# batteryboard-v2_2.net
KiCad netlist of a schematic drawn in EAGLE
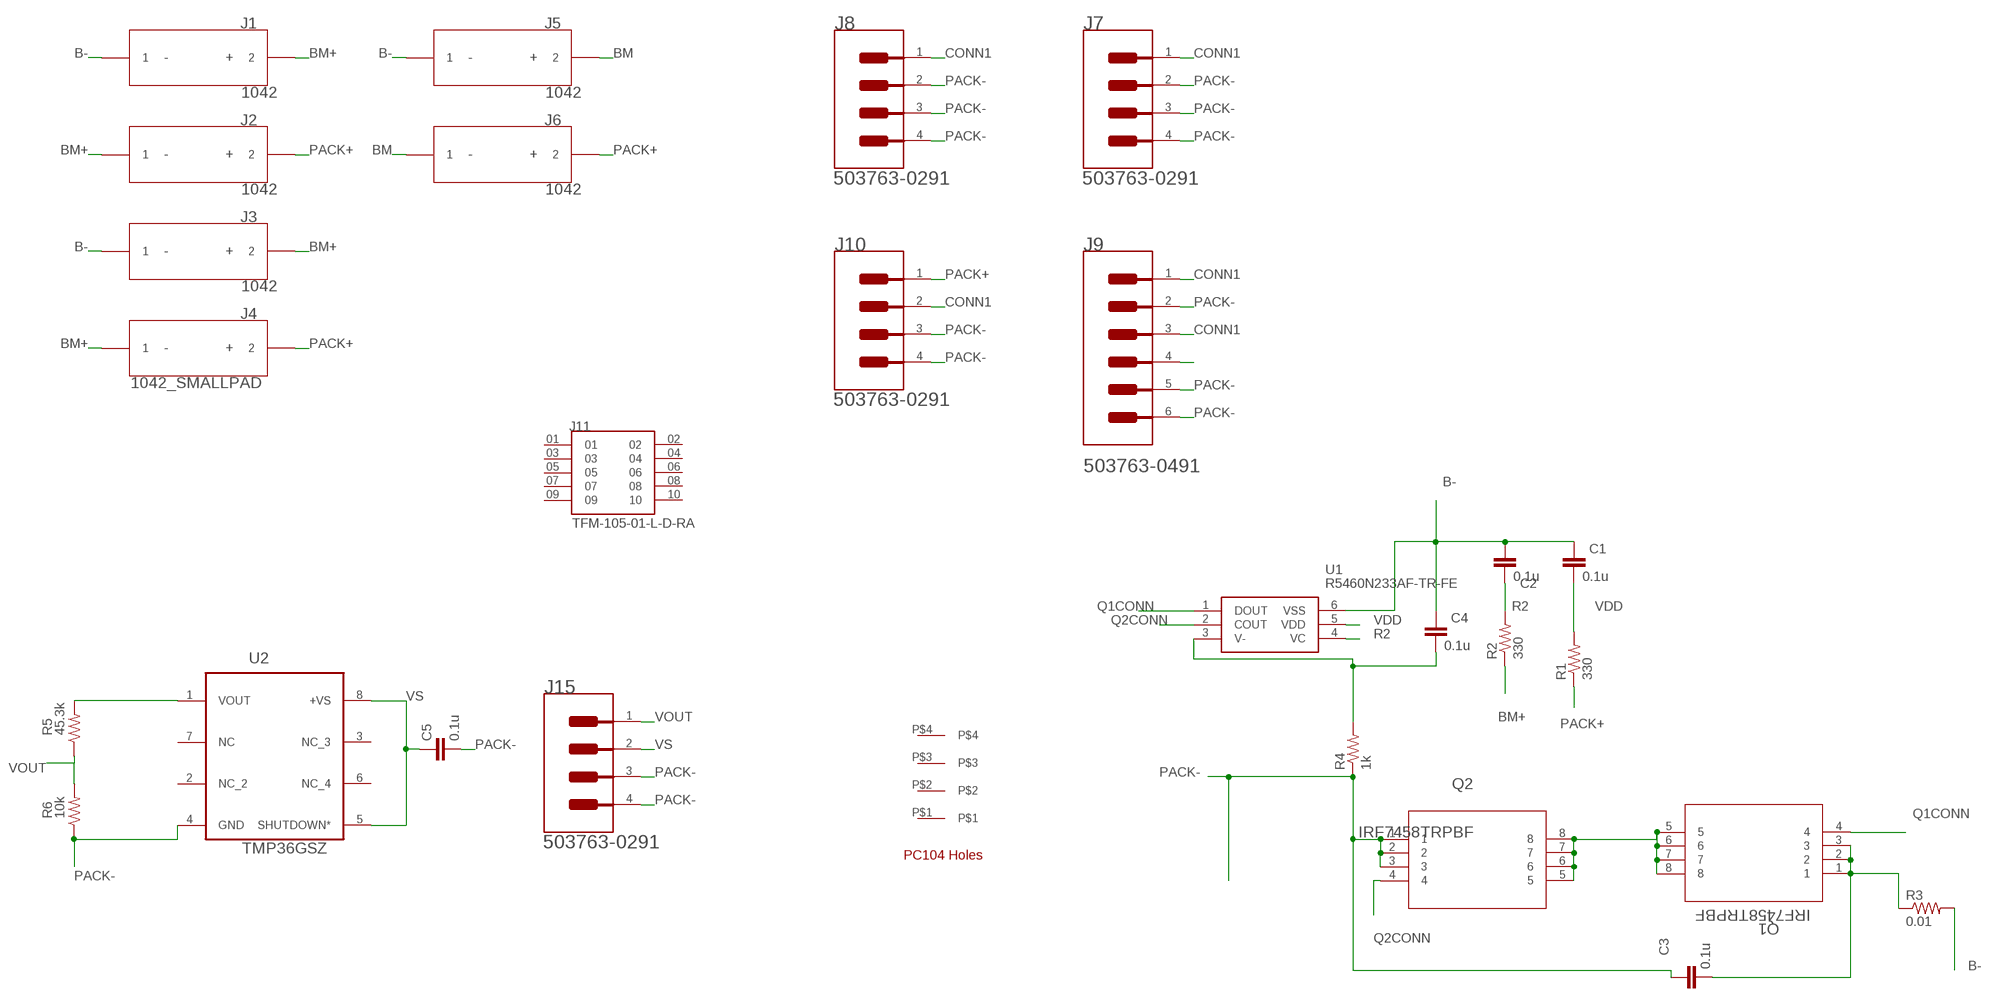
[diagram p0: schematic, sheet 1]

(export (version "E")
  (design (tool "Eeschema 10.0.6"))
  (components
    (comp (ref "C1")
      (value "0.1u")
      (footprint "eagle-import:0603-CAP")
      (libsource (lib "eagle-import") (part "CAP0603-CAP"))
    )
    (comp (ref "C2")
      (value "0.1u")
      (footprint "eagle-import:0603-CAP")
      (libsource (lib "eagle-import") (part "CAP0603-CAP"))
    )
    (comp (ref "C3")
      (value "0.1u")
      (footprint "eagle-import:0603-CAP")
      (libsource (lib "eagle-import") (part "CAP0603-CAP"))
    )
    (comp (ref "C4")
      (value "0.1u")
      (footprint "eagle-import:0603-CAP")
      (libsource (lib "eagle-import") (part "CAP0603-CAP"))
    )
    (comp (ref "C5")
      (value "0.1u")
      (footprint "eagle-import:0805")
      (libsource (lib "eagle-import") (part "CAP0805"))
    )
    (comp (ref "J1")
      (value "1042")
      (footprint "eagle-import:1042_KEY")
      (fields (field (name "COPYRIGHT") "Copyright (C) 2021 Ultra Librarian. All rights reserved."))
      (libsource (lib "eagle-import") (part "1042"))
    )
    (comp (ref "J2")
      (value "1042")
      (footprint "eagle-import:1042_KEY")
      (fields (field (name "COPYRIGHT") "Copyright (C) 2021 Ultra Librarian. All rights reserved."))
      (libsource (lib "eagle-import") (part "1042"))
    )
    (comp (ref "J3")
      (value "1042")
      (footprint "eagle-import:1042_KEY")
      (fields (field (name "COPYRIGHT") "Copyright (C) 2021 Ultra Librarian. All rights reserved."))
      (libsource (lib "eagle-import") (part "1042"))
    )
    (comp (ref "J4")
      (value "1042_SMALLPAD")
      (footprint "eagle-import:1042_KEY_SMALLPAD")
      (libsource (lib "eagle-import") (part "1042_SMALLPAD"))
    )
    (comp (ref "J5")
      (value "1042")
      (footprint "eagle-import:1042_KEY")
      (fields (field (name "COPYRIGHT") "Copyright (C) 2021 Ultra Librarian. All rights reserved."))
      (libsource (lib "eagle-import") (part "1042"))
    )
    (comp (ref "J6")
      (value "1042")
      (footprint "eagle-import:1042_KEY")
      (fields (field (name "COPYRIGHT") "Copyright (C) 2021 Ultra Librarian. All rights reserved."))
      (libsource (lib "eagle-import") (part "1042"))
    )
    (comp (ref "J7")
      (value "MOLEX_503763-0291MOLEX_503763-0291_0_0")
      (footprint "eagle-import:MOLEX_503763-0291_0")
      (fields
        (field (name "DIGIKEY_PART_NUMBER") "WM10654CT-ND")
        (field (name "MF") "Molex")
        (field (name "MOUSER_PART_NUMBER") "538-503763-0291")
      )
      (libsource (lib "eagle-import") (part "MOLEX_503763-0291MOLEX_503763-0291_0_0"))
    )
    (comp (ref "J8")
      (value "MOLEX_503763-0291MOLEX_503763-0291_0_0")
      (footprint "eagle-import:MOLEX_503763-0291_0")
      (fields
        (field (name "DIGIKEY_PART_NUMBER") "WM10654CT-ND")
        (field (name "MF") "Molex")
        (field (name "MOUSER_PART_NUMBER") "538-503763-0291")
      )
      (libsource (lib "eagle-import") (part "MOLEX_503763-0291MOLEX_503763-0291_0_0"))
    )
    (comp (ref "J9")
      (value "MOLEX_503763-0491MOLEX_503763-0491_0_0")
      (footprint "eagle-import:MOLEX_503763-0491_0")
      (fields
        (field (name "DIGIKEY_PART_NUMBER") "WM10655CT-ND")
        (field (name "MF") "Molex")
        (field (name "MOUSER_PART_NUMBER") "538-503763-0491")
      )
      (libsource (lib "eagle-import") (part "MOLEX_503763-0491MOLEX_503763-0491_0_0"))
    )
    (comp (ref "J10")
      (value "MOLEX_503763-0291MOLEX_503763-0291_0_0")
      (footprint "eagle-import:MOLEX_503763-0291_0")
      (fields
        (field (name "DIGIKEY_PART_NUMBER") "WM10654CT-ND")
        (field (name "MF") "Molex")
        (field (name "MOUSER_PART_NUMBER") "538-503763-0291")
      )
      (libsource (lib "eagle-import") (part "MOLEX_503763-0291MOLEX_503763-0291_0_0"))
    )
    (comp (ref "J11")
      (value "TFM-105-01-L-D-RA")
      (footprint "eagle-import:SAMTEC_TFM-105-01-L-D-RA")
      (fields (field (name "MANUFACTURER") "Samtec"))
      (libsource (lib "eagle-import") (part "TFM-105-01-L-D-RA"))
    )
    (comp (ref "J15")
      (value "MOLEX_503763-0291MOLEX_503763-0291_0_0")
      (footprint "eagle-import:MOLEX_503763-0291_0")
      (fields
        (field (name "DIGIKEY_PART_NUMBER") "WM10654CT-ND")
        (field (name "MF") "Molex")
        (field (name "MOUSER_PART_NUMBER") "538-503763-0291")
      )
      (libsource (lib "eagle-import") (part "MOLEX_503763-0291MOLEX_503763-0291_0_0"))
    )
    (comp (ref "Q1")
      (value "IRF7458TRPBF")
      (footprint "eagle-import:SO-8_IRF7458_3P9X4P9_INF")
      (fields (field (name "COPYRIGHT") "Copyright (C) 2021 Ultra Librarian. All rights reserved."))
      (libsource (lib "eagle-import") (part "IRF7458TRPBF"))
    )
    (comp (ref "Q2")
      (value "IRF7458TRPBF")
      (footprint "eagle-import:SO-8_IRF7458_3P9X4P9_INF")
      (fields (field (name "COPYRIGHT") "Copyright (C) 2021 Ultra Librarian. All rights reserved."))
      (libsource (lib "eagle-import") (part "IRF7458TRPBF"))
    )
    (comp (ref "R1")
      (value "330")
      (footprint "eagle-import:0603-RES")
      (libsource (lib "eagle-import") (part "RESISTOR0603-RES"))
    )
    (comp (ref "R2")
      (value "330")
      (footprint "eagle-import:0603-RES")
      (libsource (lib "eagle-import") (part "RESISTOR0603-RES"))
    )
    (comp (ref "R3")
      (value "0.01")
      (footprint "eagle-import:R2512")
      (libsource (lib "eagle-import") (part "RESISTOR2512"))
    )
    (comp (ref "R4")
      (value "1k")
      (footprint "eagle-import:0603-RES")
      (libsource (lib "eagle-import") (part "RESISTOR0603-RES"))
    )
    (comp (ref "R5")
      (value "45.3k")
      (footprint "eagle-import:0805")
      (libsource (lib "eagle-import") (part "RESISTOR0805-RES"))
    )
    (comp (ref "R6")
      (value "10k")
      (footprint "eagle-import:0805")
      (libsource (lib "eagle-import") (part "RESISTOR0805-RES"))
    )
    (comp (ref "U$1")
      (value "PC104_HOLES")
      (footprint "eagle-import:PC104_HOLES")
      (libsource (lib "eagle-import") (part "PC104_HOLES"))
    )
    (comp (ref "U1")
      (value "R5460N233AF-TR-FE")
      (footprint "eagle-import:SOT95P280X140-6N")
      (fields (field (name "MOUSER_PART_NUMBER") "848-R5460N233AFTRFE"))
      (libsource (lib "eagle-import") (part "R5460N233AF-TR-FE"))
    )
    (comp (ref "U2")
      (value "TMP36GSZ")
      (footprint "eagle-import:SOIC127P600X175-8N")
      (fields (field (name "MF") "Analog Devices"))
      (libsource (lib "eagle-import") (part "TMP36GSZ"))
    )
  )
  (nets
    (net (code "1") (name "/B-") (class "Default")
      (node (ref "C1") (pin "1") (pinfunction "1_1") (pintype "passive"))
      (node (ref "C2") (pin "1") (pinfunction "1_1") (pintype "passive"))
      (node (ref "C4") (pin "1") (pinfunction "1_1") (pintype "passive"))
      (node (ref "J1") (pin "1") (pinfunction "1_1") (pintype "passive"))
      (node (ref "J3") (pin "1") (pinfunction "1_1") (pintype "passive"))
      (node (ref "J5") (pin "1") (pinfunction "1_1") (pintype "passive"))
      (node (ref "R3") (pin "2") (pinfunction "2_2") (pintype "passive"))
      (node (ref "U1") (pin "6") (pinfunction "VSS_6") (pintype "bidirectional"))
    )
    (net (code "2") (name "/BM") (class "Default")
      (node (ref "J5") (pin "2") (pinfunction "2_2") (pintype "passive"))
      (node (ref "J6") (pin "1") (pinfunction "1_1") (pintype "passive"))
    )
    (net (code "3") (name "/BM+") (class "Default")
      (node (ref "J1") (pin "2") (pinfunction "2_2") (pintype "passive"))
      (node (ref "J2") (pin "1") (pinfunction "1_1") (pintype "passive"))
      (node (ref "J3") (pin "2") (pinfunction "2_2") (pintype "passive"))
      (node (ref "J4") (pin "1") (pinfunction "1_1") (pintype "passive"))
      (node (ref "R2") (pin "1") (pinfunction "1_1") (pintype "passive"))
    )
    (net (code "4") (name "/CONN1") (class "Default")
      (node (ref "J10") (pin "2") (pinfunction "2_2") (pintype "bidirectional"))
      (node (ref "J7") (pin "1") (pinfunction "1_1") (pintype "bidirectional"))
      (node (ref "J8") (pin "1") (pinfunction "1_1") (pintype "bidirectional"))
      (node (ref "J9") (pin "1") (pinfunction "1_1") (pintype "passive"))
      (node (ref "J9") (pin "3") (pinfunction "3_3") (pintype "passive"))
    )
    (net (code "5") (name "/PACK+") (class "Default")
      (node (ref "J10") (pin "1") (pinfunction "1_1") (pintype "bidirectional"))
      (node (ref "J2") (pin "2") (pinfunction "2_2") (pintype "passive"))
      (node (ref "J4") (pin "2") (pinfunction "2_2") (pintype "passive"))
      (node (ref "J6") (pin "2") (pinfunction "2_2") (pintype "passive"))
      (node (ref "R1") (pin "1") (pinfunction "1_1") (pintype "passive"))
    )
    (net (code "6") (name "/PACK-") (class "Default")
      (node (ref "C3") (pin "1") (pinfunction "1_1") (pintype "passive"))
      (node (ref "C5") (pin "2") (pinfunction "2_2") (pintype "passive"))
      (node (ref "J10") (pin "3") (pinfunction "MNT_1_3") (pintype "bidirectional"))
      (node (ref "J10") (pin "4") (pinfunction "MNT_2_4") (pintype "bidirectional"))
      (node (ref "J15") (pin "3") (pinfunction "MNT_1_3") (pintype "bidirectional"))
      (node (ref "J15") (pin "4") (pinfunction "MNT_2_4") (pintype "bidirectional"))
      (node (ref "J7") (pin "2") (pinfunction "2_2") (pintype "bidirectional"))
      (node (ref "J7") (pin "3") (pinfunction "MNT_1_3") (pintype "bidirectional"))
      (node (ref "J7") (pin "4") (pinfunction "MNT_2_4") (pintype "bidirectional"))
      (node (ref "J8") (pin "2") (pinfunction "2_2") (pintype "bidirectional"))
      (node (ref "J8") (pin "3") (pinfunction "MNT_1_3") (pintype "bidirectional"))
      (node (ref "J8") (pin "4") (pinfunction "MNT_2_4") (pintype "bidirectional"))
      (node (ref "J9") (pin "2") (pinfunction "2_2") (pintype "passive"))
      (node (ref "J9") (pin "4") (pinfunction "4_4") (pintype "passive"))
      (node (ref "J9") (pin "5") (pinfunction "MNT_1_5") (pintype "passive"))
      (node (ref "J9") (pin "6") (pinfunction "MNT_2_6") (pintype "passive"))
      (node (ref "Q2") (pin "1") (pinfunction "1_1") (pintype "passive"))
      (node (ref "Q2") (pin "2") (pinfunction "2_2") (pintype "passive"))
      (node (ref "Q2") (pin "3") (pinfunction "3_3") (pintype "passive"))
      (node (ref "R4") (pin "1") (pinfunction "1_1") (pintype "passive"))
      (node (ref "R6") (pin "1") (pinfunction "1_1") (pintype "passive"))
      (node (ref "U2") (pin "4") (pinfunction "GND_4") (pintype "passive"))
    )
    (net (code "7") (name "/Q1CONN") (class "Default")
      (node (ref "Q1") (pin "4") (pinfunction "4_4") (pintype "passive"))
      (node (ref "U1") (pin "1") (pinfunction "DOUT_1") (pintype "bidirectional"))
    )
    (net (code "8") (name "/Q2CONN") (class "Default")
      (node (ref "Q2") (pin "4") (pinfunction "4_4") (pintype "passive"))
      (node (ref "U1") (pin "2") (pinfunction "COUT_2") (pintype "bidirectional"))
    )
    (net (code "9") (name "/R2") (class "Default")
      (node (ref "C2") (pin "2") (pinfunction "2_2") (pintype "passive"))
      (node (ref "R2") (pin "2") (pinfunction "2_2") (pintype "passive"))
      (node (ref "U1") (pin "4") (pinfunction "VC_4") (pintype "bidirectional"))
    )
    (net (code "10") (name "/VDD") (class "Default")
      (node (ref "C1") (pin "2") (pinfunction "2_2") (pintype "passive"))
      (node (ref "R1") (pin "2") (pinfunction "2_2") (pintype "passive"))
      (node (ref "U1") (pin "5") (pinfunction "VDD_5") (pintype "bidirectional"))
    )
    (net (code "11") (name "/VOUT") (class "Default")
      (node (ref "J15") (pin "1") (pinfunction "1_1") (pintype "bidirectional"))
      (node (ref "R5") (pin "1") (pinfunction "1_1") (pintype "passive"))
      (node (ref "R6") (pin "2") (pinfunction "2_2") (pintype "passive"))
    )
    (net (code "12") (name "/VS") (class "Default")
      (node (ref "C5") (pin "1") (pinfunction "1_1") (pintype "passive"))
      (node (ref "J15") (pin "2") (pinfunction "2_2") (pintype "bidirectional"))
      (node (ref "U2") (pin "5") (pinfunction "SHUTDOWN*_5") (pintype "passive"))
      (node (ref "U2") (pin "8") (pinfunction "+VS_8") (pintype "power_in"))
    )
    (net (code "13") (name "Net-(C3-Pad2)") (class "Default")
      (node (ref "C3") (pin "2") (pinfunction "2_2") (pintype "passive"))
      (node (ref "Q1") (pin "1") (pinfunction "1_1") (pintype "passive"))
      (node (ref "Q1") (pin "2") (pinfunction "2_2") (pintype "passive"))
      (node (ref "Q1") (pin "3") (pinfunction "3_3") (pintype "passive"))
      (node (ref "R3") (pin "1") (pinfunction "1_1") (pintype "passive"))
    )
    (net (code "14") (name "Net-(Q1-Pad5)") (class "Default")
      (node (ref "Q1") (pin "5") (pinfunction "5_5") (pintype "passive"))
      (node (ref "Q1") (pin "6") (pinfunction "6_6") (pintype "passive"))
      (node (ref "Q1") (pin "7") (pinfunction "7_7") (pintype "passive"))
      (node (ref "Q1") (pin "8") (pinfunction "8_8") (pintype "passive"))
      (node (ref "Q2") (pin "5") (pinfunction "5_5") (pintype "passive"))
      (node (ref "Q2") (pin "6") (pinfunction "6_6") (pintype "passive"))
      (node (ref "Q2") (pin "7") (pinfunction "7_7") (pintype "passive"))
      (node (ref "Q2") (pin "8") (pinfunction "8_8") (pintype "passive"))
    )
    (net (code "15") (name "Net-(U1-V-)") (class "Default")
      (node (ref "C4") (pin "2") (pinfunction "2_2") (pintype "passive"))
      (node (ref "R4") (pin "2") (pinfunction "2_2") (pintype "passive"))
      (node (ref "U1") (pin "3") (pinfunction "V-_3") (pintype "bidirectional"))
    )
    (net (code "16") (name "Net-(U2-VOUT)") (class "Default")
      (node (ref "R5") (pin "2") (pinfunction "2_2") (pintype "passive"))
      (node (ref "U2") (pin "1") (pinfunction "VOUT_1") (pintype "passive"))
    )
    (net (code "17") (name "unconnected-(J11-Pad01)") (class "Default")
      (node (ref "J11") (pin "01") (pinfunction "01_01") (pintype "passive"))
    )
    (net (code "18") (name "unconnected-(J11-Pad02)") (class "Default")
      (node (ref "J11") (pin "02") (pinfunction "02_02") (pintype "passive"))
    )
    (net (code "19") (name "unconnected-(J11-Pad03)") (class "Default")
      (node (ref "J11") (pin "03") (pinfunction "03_03") (pintype "passive"))
    )
    (net (code "20") (name "unconnected-(J11-Pad04)") (class "Default")
      (node (ref "J11") (pin "04") (pinfunction "04_04") (pintype "passive"))
    )
    (net (code "21") (name "unconnected-(J11-Pad05)") (class "Default")
      (node (ref "J11") (pin "05") (pinfunction "05_05") (pintype "passive"))
    )
    (net (code "22") (name "unconnected-(J11-Pad06)") (class "Default")
      (node (ref "J11") (pin "06") (pinfunction "06_06") (pintype "passive"))
    )
    (net (code "23") (name "unconnected-(J11-Pad07)") (class "Default")
      (node (ref "J11") (pin "07") (pinfunction "07_07") (pintype "passive"))
    )
    (net (code "24") (name "unconnected-(J11-Pad08)") (class "Default")
      (node (ref "J11") (pin "08") (pinfunction "08_08") (pintype "passive"))
    )
    (net (code "25") (name "unconnected-(J11-Pad09)") (class "Default")
      (node (ref "J11") (pin "09") (pinfunction "09_09") (pintype "passive"))
    )
    (net (code "26") (name "unconnected-(J11-Pad10)") (class "Default")
      (node (ref "J11") (pin "10") (pinfunction "10_10") (pintype "passive"))
    )
    (net (code "27") (name "unconnected-(U$1-PadP$1)") (class "Default")
      (node (ref "U$1") (pin "P$1") (pinfunction "P$1_P$1") (pintype "bidirectional"))
    )
    (net (code "28") (name "unconnected-(U$1-PadP$2)") (class "Default")
      (node (ref "U$1") (pin "P$2") (pinfunction "P$2_P$2") (pintype "bidirectional"))
    )
    (net (code "29") (name "unconnected-(U$1-PadP$3)") (class "Default")
      (node (ref "U$1") (pin "P$3") (pinfunction "P$3_P$3") (pintype "bidirectional"))
    )
    (net (code "30") (name "unconnected-(U$1-PadP$4)") (class "Default")
      (node (ref "U$1") (pin "P$4") (pinfunction "P$4_P$4") (pintype "bidirectional"))
    )
    (net (code "31") (name "unconnected-(U2-NC-Pad7)") (class "Default")
      (node (ref "U2") (pin "7") (pinfunction "NC_7") (pintype "passive"))
    )
    (net (code "32") (name "unconnected-(U2-NC_2-Pad2)") (class "Default")
      (node (ref "U2") (pin "2") (pinfunction "NC_2_2") (pintype "passive"))
    )
    (net (code "33") (name "unconnected-(U2-NC_3-Pad3)") (class "Default")
      (node (ref "U2") (pin "3") (pinfunction "NC_3_3") (pintype "passive"))
    )
    (net (code "34") (name "unconnected-(U2-NC_4-Pad6)") (class "Default")
      (node (ref "U2") (pin "6") (pinfunction "NC_4_6") (pintype "passive"))
    )
  )
)
